# DIGISPARK_PRODUCTION_REV3.net
KiCad netlist of a schematic drawn in EAGLE
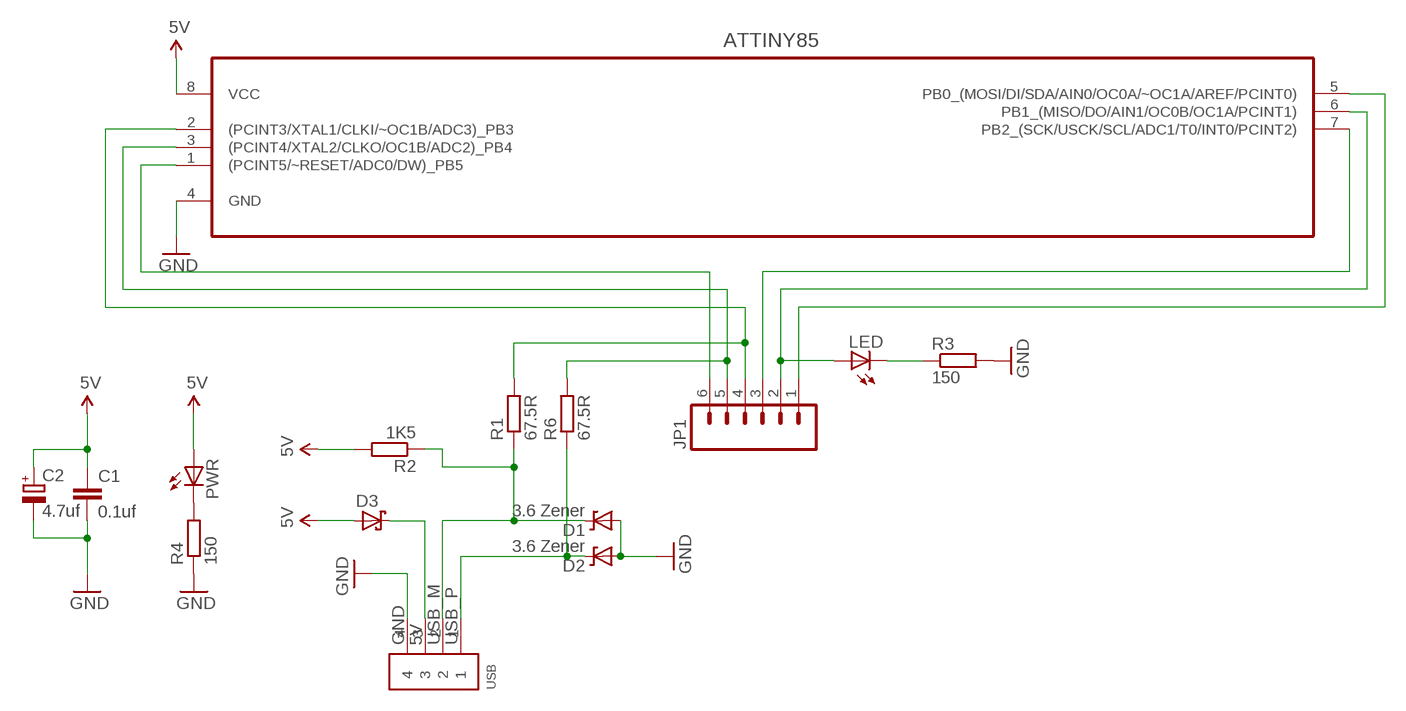
[diagram p0: schematic, sheet 1]

(export (version "E")
  (design (tool "Eeschema 10.0.6"))
  (components
    (comp (ref "ATTINY85")
      (value "ATTINY85-20PU")
      (footprint "eagle-import:DIP254P762X533-8")
      (libsource (lib "eagle-import") (part "ATTINY85-20PU"))
    )
    (comp (ref "C1")
      (value "0.1uf")
      (footprint "eagle-import:C050-045X075")
      (libsource (lib "eagle-import") (part "C-EU050-045X075"))
    )
    (comp (ref "C2")
      (value "4.7uf")
      (footprint "eagle-import:E5-4")
      (libsource (lib "eagle-import") (part "CPOL-EUE5-4"))
    )
    (comp (ref "D1")
      (value "3.6 Zener")
      (footprint "eagle-import:DIODE-ZENER")
      (libsource (lib "eagle-import") (part "DIODE-ZENERPTH"))
    )
    (comp (ref "D2")
      (value "3.6 Zener")
      (footprint "eagle-import:DIODE-ZENER")
      (libsource (lib "eagle-import") (part "DIODE-ZENERPTH"))
    )
    (comp (ref "D3")
      (value "SCHOTTKY-DIODEDO35-7")
      (footprint "eagle-import:DO35-7")
      (libsource (lib "eagle-import") (part "SCHOTTKY-DIODEDO35-7"))
    )
    (comp (ref "JP1")
      (value "M06SIP")
      (footprint "eagle-import:1X06")
      (libsource (lib "eagle-import") (part "M06SIP"))
    )
    (comp (ref "LED")
      (value "LED5MM")
      (footprint "eagle-import:LED5MM")
      (libsource (lib "eagle-import") (part "LED5MM"))
    )
    (comp (ref "PWR")
      (value "LED5MM")
      (footprint "eagle-import:LED5MM")
      (libsource (lib "eagle-import") (part "LED5MM"))
    )
    (comp (ref "R1")
      (value "67.5R")
      (footprint "eagle-import:0207_12")
      (libsource (lib "eagle-import") (part "R-EU_0207/12"))
    )
    (comp (ref "R2")
      (value "1K5")
      (footprint "eagle-import:0207_12")
      (libsource (lib "eagle-import") (part "R-EU_0207/12"))
    )
    (comp (ref "R3")
      (value "150")
      (footprint "eagle-import:0207_12")
      (libsource (lib "eagle-import") (part "R-EU_0207/12"))
    )
    (comp (ref "R4")
      (value "150")
      (footprint "eagle-import:0207_12")
      (libsource (lib "eagle-import") (part "R-EU_0207/12"))
    )
    (comp (ref "R6")
      (value "67.5R")
      (footprint "eagle-import:0207_12")
      (libsource (lib "eagle-import") (part "R-EU_0207/12"))
    )
    (comp (ref "USB")
      (value "1X4-CLEANBIG")
      (footprint "eagle-import:1X04-CLEANBIG")
      (fields
        (field (name "1") "GND")
        (field (name "2") "5V")
        (field (name "3") "USB_M")
        (field (name "4") "USB_P")
      )
      (libsource (lib "eagle-import") (part "1X4-CLEANBIG"))
    )
  )
  (nets
    (net (code "1") (name "5V") (class "Default")
      (node (ref "ATTINY85") (pin "8") (pinfunction "VCC_8") (pintype "power_in"))
      (node (ref "C1") (pin "1") (pinfunction "1_1") (pintype "passive"))
      (node (ref "C2") (pin "+") (pinfunction "+_+") (pintype "passive"))
      (node (ref "D3") (pin "A") (pinfunction "A_A") (pintype "passive"))
      (node (ref "PWR") (pin "A") (pinfunction "A_A") (pintype "passive"))
      (node (ref "R2") (pin "2") (pinfunction "2_2") (pintype "passive"))
    )
    (net (code "2") (name "GND") (class "Default")
      (node (ref "ATTINY85") (pin "4") (pinfunction "GND_4") (pintype "passive"))
      (node (ref "C1") (pin "2") (pinfunction "2_2") (pintype "passive"))
      (node (ref "C2") (pin "-") (pinfunction "-_-") (pintype "passive"))
      (node (ref "D1") (pin "P$2") (pinfunction "A_P$2") (pintype "passive"))
      (node (ref "D2") (pin "P$2") (pinfunction "A_P$2") (pintype "passive"))
      (node (ref "R3") (pin "2") (pinfunction "2_2") (pintype "passive"))
      (node (ref "R4") (pin "1") (pinfunction "1_1") (pintype "passive"))
      (node (ref "USB") (pin "4") (pinfunction "4_4") (pintype "bidirectional"))
    )
    (net (code "3") (name "Net-(ATTINY85-(PCINT3{slash}XTAL1{slash}CLKI{slash}~{OC1B{slash}ADC3})_PB3)") (class "Default")
      (node (ref "ATTINY85") (pin "2") (pinfunction "(PCINT3/XTAL1/CLKI/~{OC1B/ADC3})_PB3_2") (pintype "bidirectional"))
      (node (ref "JP1") (pin "4") (pinfunction "4_4") (pintype "passive"))
      (node (ref "R1") (pin "2") (pinfunction "2_2") (pintype "passive"))
    )
    (net (code "4") (name "Net-(ATTINY85-(PCINT4{slash}XTAL2{slash}CLKO{slash}OC1B{slash}ADC2)_PB4)") (class "Default")
      (node (ref "ATTINY85") (pin "3") (pinfunction "(PCINT4/XTAL2/CLKO/OC1B/ADC2)_PB4_3") (pintype "bidirectional"))
      (node (ref "JP1") (pin "5") (pinfunction "5_5") (pintype "passive"))
      (node (ref "R6") (pin "2") (pinfunction "2_2") (pintype "passive"))
    )
    (net (code "5") (name "Net-(ATTINY85-(PCINT5{slash}~{RESET{slash}ADC0{slash}DW})_PB5)") (class "Default")
      (node (ref "ATTINY85") (pin "1") (pinfunction "(PCINT5/~{RESET/ADC0/DW})_PB5_1") (pintype "bidirectional"))
      (node (ref "JP1") (pin "6") (pinfunction "6_6") (pintype "passive"))
    )
    (net (code "6") (name "Net-(ATTINY85-PB0_(MOSI{slash}DI{slash}SDA{slash}AIN0{slash}OC0A{slash}~{OC1A{slash}AREF{slash}PCINT0}))") (class "Default")
      (node (ref "ATTINY85") (pin "5") (pinfunction "PB0_(MOSI/DI/SDA/AIN0/OC0A/~{OC1A/AREF/PCINT0})_5") (pintype "bidirectional"))
      (node (ref "JP1") (pin "1") (pinfunction "1_1") (pintype "passive"))
    )
    (net (code "7") (name "Net-(ATTINY85-PB1_(MISO{slash}DO{slash}AIN1{slash}OC0B{slash}OC1A{slash}PCINT1))") (class "Default")
      (node (ref "ATTINY85") (pin "6") (pinfunction "PB1_(MISO/DO/AIN1/OC0B/OC1A/PCINT1)_6") (pintype "bidirectional"))
      (node (ref "JP1") (pin "2") (pinfunction "2_2") (pintype "passive"))
      (node (ref "LED") (pin "A") (pinfunction "A_A") (pintype "passive"))
    )
    (net (code "8") (name "Net-(ATTINY85-PB2_(SCK{slash}USCK{slash}SCL{slash}ADC1{slash}T0{slash}INT0{slash}PCINT2))") (class "Default")
      (node (ref "ATTINY85") (pin "7") (pinfunction "PB2_(SCK/USCK/SCL/ADC1/T0/INT0/PCINT2)_7") (pintype "bidirectional"))
      (node (ref "JP1") (pin "3") (pinfunction "3_3") (pintype "passive"))
    )
    (net (code "9") (name "Net-(D1-C)") (class "Default")
      (node (ref "D1") (pin "P$1") (pinfunction "C_P$1") (pintype "passive"))
      (node (ref "R1") (pin "1") (pinfunction "1_1") (pintype "passive"))
      (node (ref "R2") (pin "1") (pinfunction "1_1") (pintype "passive"))
      (node (ref "USB") (pin "2") (pinfunction "2_2") (pintype "bidirectional"))
    )
    (net (code "10") (name "Net-(D2-C)") (class "Default")
      (node (ref "D2") (pin "P$1") (pinfunction "C_P$1") (pintype "passive"))
      (node (ref "R6") (pin "1") (pinfunction "1_1") (pintype "passive"))
      (node (ref "USB") (pin "1") (pinfunction "1_1") (pintype "bidirectional"))
    )
    (net (code "11") (name "Net-(D3-PadC)") (class "Default")
      (node (ref "D3") (pin "C") (pinfunction "C_C") (pintype "passive"))
      (node (ref "USB") (pin "3") (pinfunction "3_3") (pintype "bidirectional"))
    )
    (net (code "12") (name "Net-(LED-C)") (class "Default")
      (node (ref "LED") (pin "K") (pinfunction "C_K") (pintype "passive"))
      (node (ref "R3") (pin "1") (pinfunction "1_1") (pintype "passive"))
    )
    (net (code "13") (name "Net-(PWR-C)") (class "Default")
      (node (ref "PWR") (pin "K") (pinfunction "C_K") (pintype "passive"))
      (node (ref "R4") (pin "2") (pinfunction "2_2") (pintype "passive"))
    )
  )
)
